# updated_loraxbee_ldo_sheet.net
KiCad netlist of a schematic drawn in Altium Designer
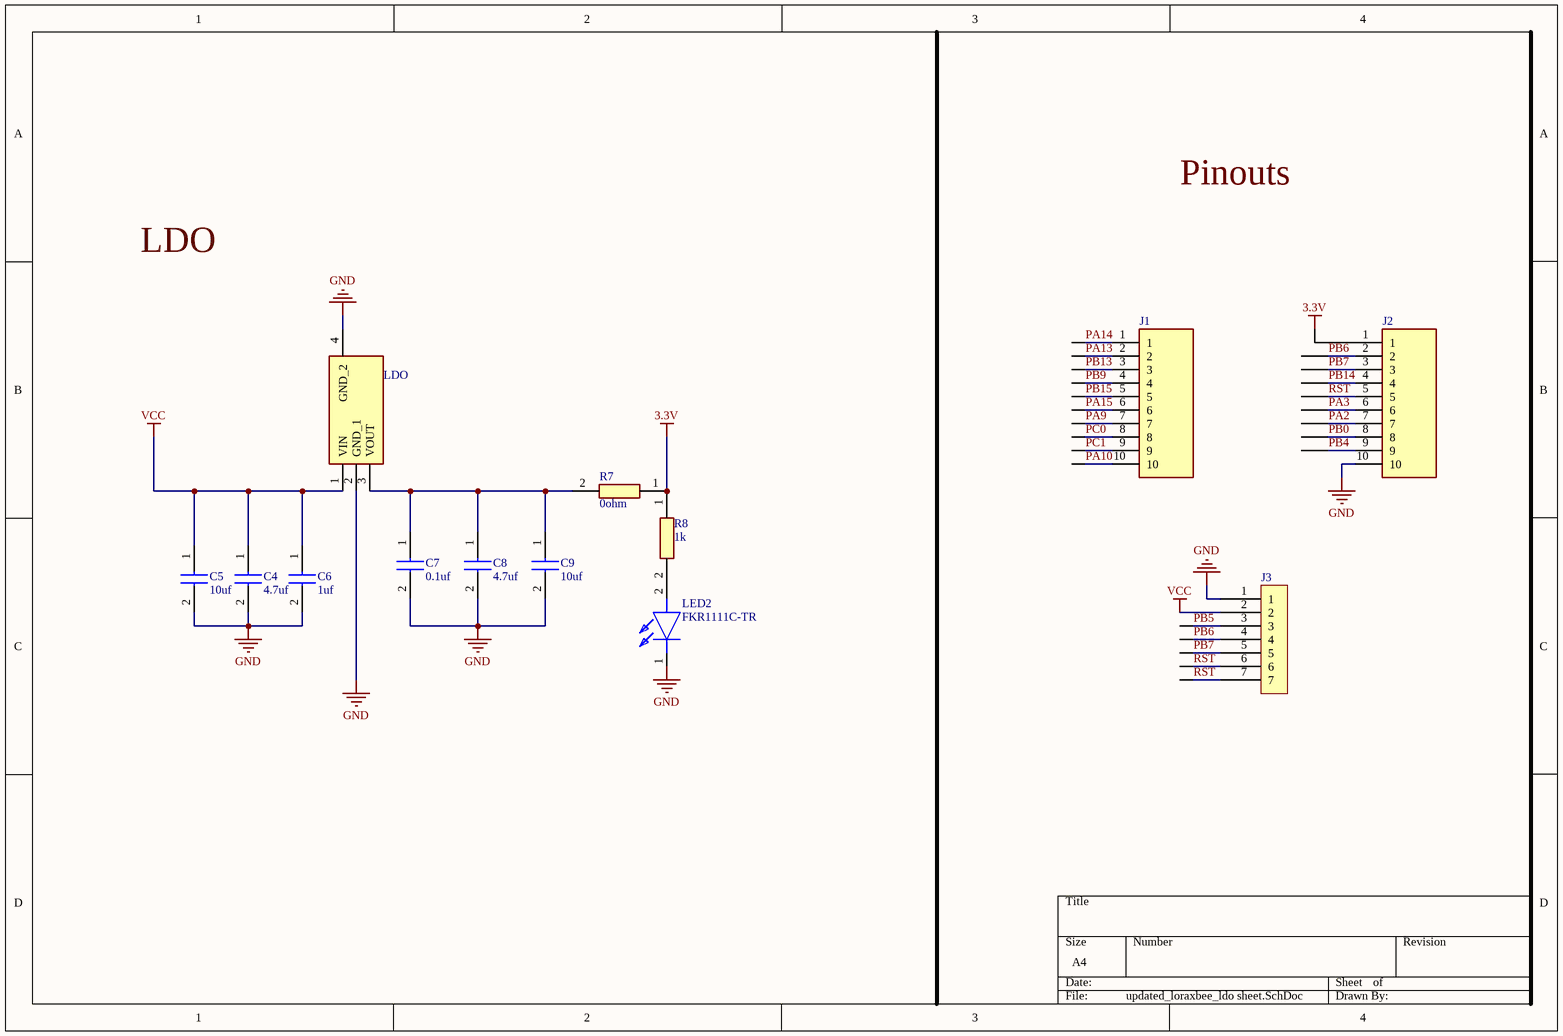
[diagram p0: updated_loraxbee_ldo sheet.SchDoc]

(export (version "E")
  (design (tool "Eeschema 10.0.6"))
  (components
    (comp (ref "C4")
      (value "4.7uf")
      (footprint "SamacSys:CAPC1608X100N")
      (description "Capacitor")
      (fields
        (field (name "MANUFACTURER_PART_NUMBER") "GCJ188C70J475KE02D")
        (field (name "MOUSER PART NUMBER") "81-GCJ188C70J475KE2D")
      )
      (libsource (lib "SamacSys") (part "GCJ188C70J475KE02D"))
    )
    (comp (ref "C5")
      (value "10uf")
      (footprint "SamacSys:CAPC1608X100N")
      (description "Capacitor")
      (fields
        (field (name "MANUFACTURER_PART_NUMBER") "GCJ188C70J475KE02D")
        (field (name "MOUSER PART NUMBER") "81-GCJ188C70J475KE2D")
      )
      (libsource (lib "SamacSys") (part "GCJ188C70J475KE02D"))
    )
    (comp (ref "C6")
      (value "1uf")
      (footprint "SamacSys:CAPC1608X100N")
      (description "Capacitor")
      (fields
        (field (name "MANUFACTURER_PART_NUMBER") "GCJ188C70J475KE02D")
        (field (name "MOUSER PART NUMBER") "81-GCJ188C70J475KE2D")
      )
      (libsource (lib "SamacSys") (part "GCJ188C70J475KE02D"))
    )
    (comp (ref "C7")
      (value "0.1uf")
      (footprint "SamacSys:CAPC1608X100N")
      (description "Capacitor")
      (fields
        (field (name "MANUFACTURER_PART_NUMBER") "GCJ188C70J475KE02D")
        (field (name "MOUSER PART NUMBER") "81-GCJ188C70J475KE2D")
      )
      (libsource (lib "SamacSys") (part "GCJ188C70J475KE02D"))
    )
    (comp (ref "C8")
      (value "4.7uf")
      (footprint "SamacSys:CAPC1608X100N")
      (description "Capacitor")
      (fields
        (field (name "MANUFACTURER_PART_NUMBER") "GCJ188C70J475KE02D")
        (field (name "MOUSER PART NUMBER") "81-GCJ188C70J475KE2D")
      )
      (libsource (lib "SamacSys") (part "GCJ188C70J475KE02D"))
    )
    (comp (ref "C9")
      (value "10uf")
      (footprint "SamacSys:CAPC1608X100N")
      (description "Capacitor")
      (fields
        (field (name "MANUFACTURER_PART_NUMBER") "GCJ188C70J475KE02D")
        (field (name "MOUSER PART NUMBER") "81-GCJ188C70J475KE2D")
      )
      (libsource (lib "SamacSys") (part "GCJ188C70J475KE02D"))
    )
    (comp (ref "J1")
      (value "2MM-HB-S10-VT-02-H-TB")
      (footprint "SamacSys:HDRV10W53P0X200_1X10_1980X200X555P")
      (description "Connector")
      (fields (field (name "MOUSER PART NUMBER") "571-2MM-HBS10VT02HTB"))
      (libsource (lib "SamacSys") (part "2MM-HB-S10-VT-02-H-TB"))
    )
    (comp (ref "J2")
      (value "2MM-HB-S10-VT-02-H-TB")
      (footprint "SamacSys:HDRV10W53P0X200_1X10_1980X200X555P")
      (description "Connector")
      (fields (field (name "MOUSER PART NUMBER") "571-2MM-HBS10VT02HTB"))
      (libsource (lib "SamacSys") (part "2MM-HB-S10-VT-02-H-TB"))
    )
    (comp (ref "J3")
      (value "7 pin 2.54mm pitch header")
      (footprint "2.5mm 7 pin header")
      (libsource (lib "7pin header 2.5mm pitch") (part "7 pin 2.54mm pitch header"))
    )
    (comp (ref "LDO")
      (value "TC1264-3.3VDB")
      (footprint "SamacSys:SOT230P700X180-4N")
      (description "Integrated Circuit")
      (fields (field (name "MOUSER PART NUMBER") "579-TC1264-3.3VDB"))
      (libsource (lib "SamacSys") (part "TC1264-3.3VDB"))
    )
    (comp (ref "LED2")
      (value "FKR1111C-TR")
      (footprint "LED-0603-BLUE")
      (description "LED")
      (fields (field (name "MOUSER PART NUMBER") "327-FKR1111CTR"))
      (libsource (lib "SamacSys") (part "FKR1111C-TR"))
    )
    (comp (ref "R7")
      (value "0ohm")
      (footprint "SamacSys:RESC1608X55N")
      (description "Resistor")
      (fields
        (field (name "MANUFACTURER_PART_NUMBER") "MCT0603HZ0000ZP500")
        (field (name "MOUSER PART NUMBER") "594-MCT0603HZ0000ZP5")
      )
      (libsource (lib "") (part "MCT0603HZ0000ZP500_1"))
    )
    (comp (ref "R8")
      (value "1k")
      (footprint "SamacSys:RESC1608X55N")
      (description "Resistor")
      (fields
        (field (name "MANUFACTURER_PART_NUMBER") "MCT0603HZ0000ZP500")
        (field (name "MOUSER PART NUMBER") "594-MCT0603HZ0000ZP5")
      )
      (libsource (lib "SamacSys") (part "MCT0603HZ0000ZP500"))
    )
  )
  (nets
    (net (code "1") (name "/PA2") (class "Default")
      (node (ref "J2") (pin "7") (pinfunction "7_7") (pintype "passive"))
    )
    (net (code "2") (name "/PA3") (class "Default")
      (node (ref "J2") (pin "6") (pinfunction "6_6") (pintype "passive"))
    )
    (net (code "3") (name "/PA9") (class "Default")
      (node (ref "J1") (pin "7") (pinfunction "7_7") (pintype "passive"))
    )
    (net (code "4") (name "/PA10") (class "Default")
      (node (ref "J1") (pin "10") (pinfunction "10_10") (pintype "passive"))
    )
    (net (code "5") (name "/PA13") (class "Default")
      (node (ref "J1") (pin "2") (pinfunction "2_2") (pintype "passive"))
    )
    (net (code "6") (name "/PA14") (class "Default")
      (node (ref "J1") (pin "1") (pinfunction "1_1") (pintype "passive"))
    )
    (net (code "7") (name "/PA15") (class "Default")
      (node (ref "J1") (pin "6") (pinfunction "6_6") (pintype "passive"))
    )
    (net (code "8") (name "/PB0") (class "Default")
      (node (ref "J2") (pin "8") (pinfunction "8_8") (pintype "passive"))
    )
    (net (code "9") (name "/PB4") (class "Default")
      (node (ref "J2") (pin "9") (pinfunction "9_9") (pintype "passive"))
    )
    (net (code "10") (name "/PB5") (class "Default")
      (node (ref "J3") (pin "3") (pinfunction "3_3") (pintype "passive"))
    )
    (net (code "11") (name "/PB6") (class "Default")
      (node (ref "J2") (pin "2") (pinfunction "2_2") (pintype "passive"))
      (node (ref "J3") (pin "4") (pinfunction "4_4") (pintype "passive"))
    )
    (net (code "12") (name "/PB7") (class "Default")
      (node (ref "J2") (pin "3") (pinfunction "3_3") (pintype "passive"))
      (node (ref "J3") (pin "5") (pinfunction "5_5") (pintype "passive"))
    )
    (net (code "13") (name "/PB9") (class "Default")
      (node (ref "J1") (pin "4") (pinfunction "4_4") (pintype "passive"))
    )
    (net (code "14") (name "/PB13") (class "Default")
      (node (ref "J1") (pin "3") (pinfunction "3_3") (pintype "passive"))
    )
    (net (code "15") (name "/PB14") (class "Default")
      (node (ref "J2") (pin "4") (pinfunction "4_4") (pintype "passive"))
    )
    (net (code "16") (name "/PB15") (class "Default")
      (node (ref "J1") (pin "5") (pinfunction "5_5") (pintype "passive"))
    )
    (net (code "17") (name "/PC0") (class "Default")
      (node (ref "J1") (pin "8") (pinfunction "8_8") (pintype "passive"))
    )
    (net (code "18") (name "/PC1") (class "Default")
      (node (ref "J1") (pin "9") (pinfunction "9_9") (pintype "passive"))
    )
    (net (code "19") (name "/RST") (class "Default")
      (node (ref "J2") (pin "5") (pinfunction "5_5") (pintype "passive"))
      (node (ref "J3") (pin "6") (pinfunction "6_6") (pintype "passive"))
      (node (ref "J3") (pin "7") (pinfunction "7_7") (pintype "passive"))
    )
    (net (code "20") (name "3.3V") (class "Default")
      (node (ref "J2") (pin "1") (pinfunction "1_1") (pintype "passive"))
      (node (ref "R7") (pin "1") (pinfunction "1_1") (pintype "passive"))
      (node (ref "R8") (pin "1") (pinfunction "1_1") (pintype "passive"))
    )
    (net (code "21") (name "GND") (class "Default")
      (node (ref "C4") (pin "2") (pinfunction "2_2") (pintype "passive"))
      (node (ref "C5") (pin "2") (pinfunction "2_2") (pintype "passive"))
      (node (ref "C6") (pin "2") (pinfunction "2_2") (pintype "passive"))
      (node (ref "C7") (pin "2") (pinfunction "2_2") (pintype "passive"))
      (node (ref "C8") (pin "2") (pinfunction "2_2") (pintype "passive"))
      (node (ref "C9") (pin "2") (pinfunction "2_2") (pintype "passive"))
      (node (ref "J2") (pin "10") (pinfunction "10_10") (pintype "passive"))
      (node (ref "J3") (pin "1") (pinfunction "1_1") (pintype "passive"))
      (node (ref "LDO") (pin "2") (pinfunction "GND_1_2") (pintype "passive"))
      (node (ref "LDO") (pin "4") (pinfunction "GND_2_4") (pintype "passive"))
      (node (ref "LED2") (pin "1") (pinfunction "K_1") (pintype "passive"))
    )
    (net (code "22") (name "Net-(LDO-VOUT)") (class "Default")
      (node (ref "C7") (pin "1") (pinfunction "1_1") (pintype "passive"))
      (node (ref "C8") (pin "1") (pinfunction "1_1") (pintype "passive"))
      (node (ref "C9") (pin "1") (pinfunction "1_1") (pintype "passive"))
      (node (ref "LDO") (pin "3") (pinfunction "VOUT_3") (pintype "passive"))
      (node (ref "R7") (pin "2") (pinfunction "2_2") (pintype "passive"))
    )
    (net (code "23") (name "Net-(LED2-A)") (class "Default")
      (node (ref "LED2") (pin "2") (pinfunction "A_2") (pintype "passive"))
      (node (ref "R8") (pin "2") (pinfunction "2_2") (pintype "passive"))
    )
    (net (code "24") (name "VCC") (class "Default")
      (node (ref "C4") (pin "1") (pinfunction "1_1") (pintype "passive"))
      (node (ref "C5") (pin "1") (pinfunction "1_1") (pintype "passive"))
      (node (ref "C6") (pin "1") (pinfunction "1_1") (pintype "passive"))
      (node (ref "J3") (pin "2") (pinfunction "2_2") (pintype "passive"))
      (node (ref "LDO") (pin "1") (pinfunction "VIN_1") (pintype "passive"))
    )
  )
)
